# 03_Power.net
KiCad netlist of a schematic drawn in Altium Designer
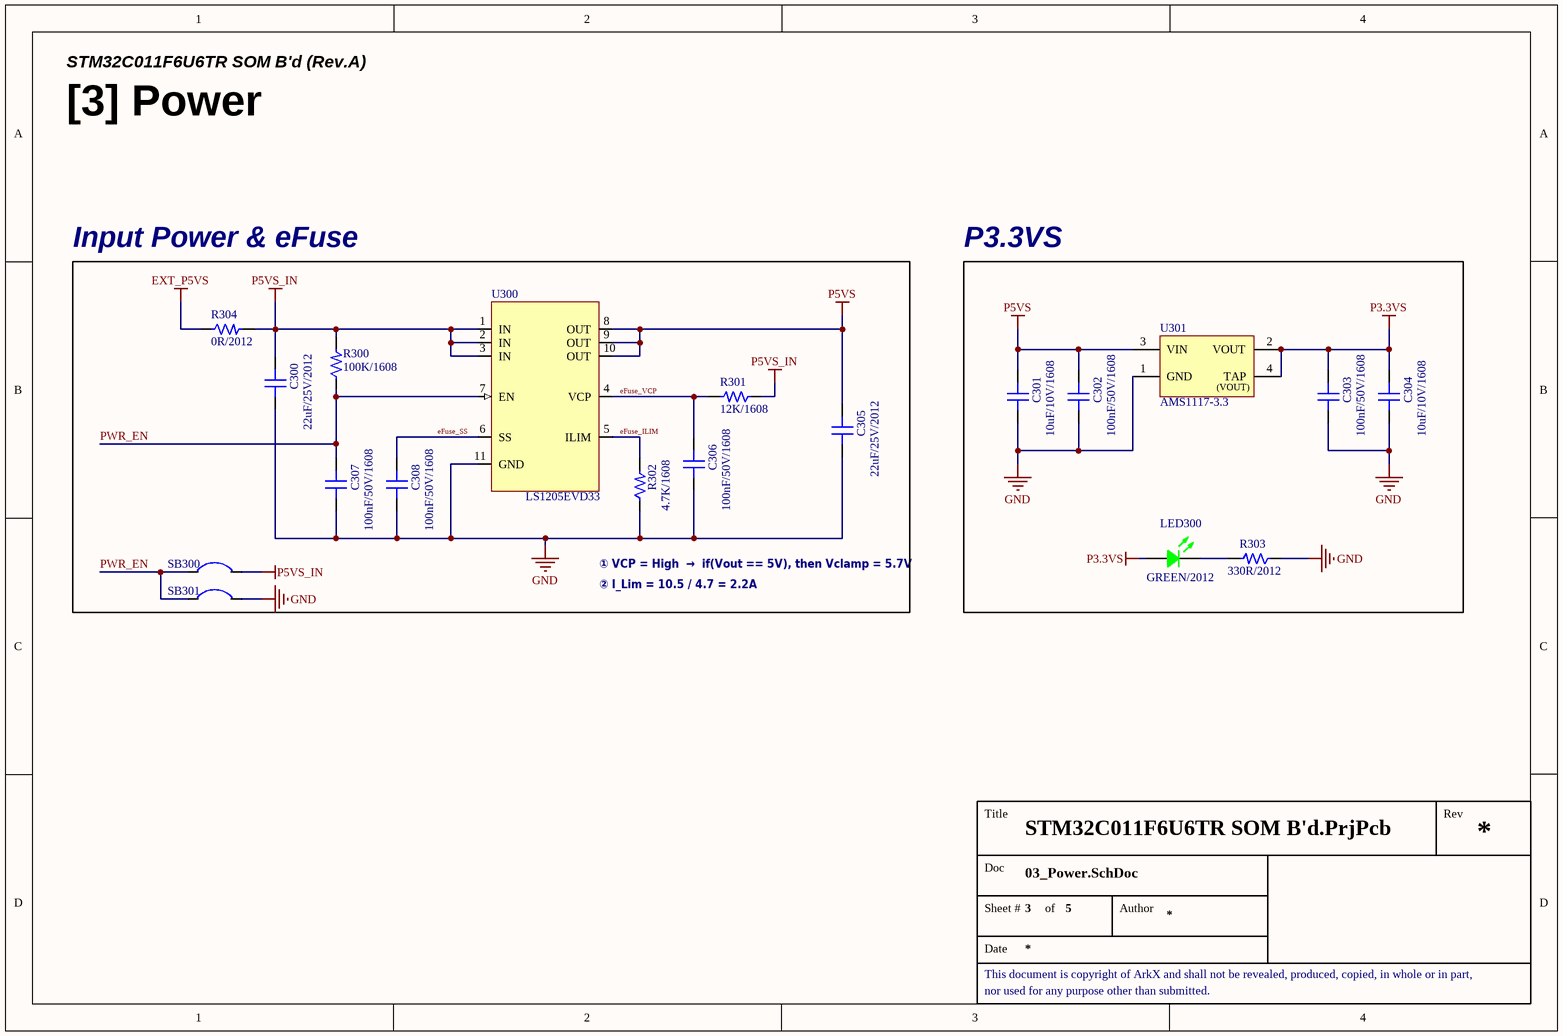
[diagram p0: 03_Power.SchDoc]

(export (version "E")
  (design (tool "Eeschema 10.0.6"))
  (components
    (comp (ref "C300")
      (value "22uF/25V/2012")
      (footprint "CAP 2012 (0805_INCH)")
      (description "Ceramic CAP_22uF/25V/2012")
      (fields (field (name "LCSC PART #") "C45783"))
      (libsource (lib "Arkx") (part "CAP_22uF/25V/2012"))
    )
    (comp (ref "C301")
      (value "10uF/10V/1608")
      (footprint "CAP 1608 (0603_INCH)")
      (description "Ceramic CAP_10uF/10V/1608")
      (fields (field (name "LCSC PART #") "C19702"))
      (libsource (lib "Arkx") (part "CAP_10uF/10V/1608"))
    )
    (comp (ref "C302")
      (value "100nF/50V/1608")
      (footprint "CAP 1608 (0603_INCH)")
      (description "Ceramic CAP_100nF/50V/1608")
      (fields (field (name "LCSC PART #") "C14663"))
      (libsource (lib "Arkx") (part "CAP_100nF/50V/1608"))
    )
    (comp (ref "C303")
      (value "100nF/50V/1608")
      (footprint "CAP 1608 (0603_INCH)")
      (description "Ceramic CAP_100nF/50V/1608")
      (fields (field (name "LCSC PART #") "C14663"))
      (libsource (lib "Arkx") (part "CAP_100nF/50V/1608"))
    )
    (comp (ref "C304")
      (value "10uF/10V/1608")
      (footprint "CAP 1608 (0603_INCH)")
      (description "Ceramic CAP_10uF/10V/1608")
      (fields (field (name "LCSC PART #") "C19702"))
      (libsource (lib "Arkx") (part "CAP_10uF/10V/1608"))
    )
    (comp (ref "C305")
      (value "22uF/25V/2012")
      (footprint "CAP 2012 (0805_INCH)")
      (description "Ceramic CAP_22uF/25V/2012")
      (fields (field (name "LCSC PART #") "C45783"))
      (libsource (lib "Arkx") (part "CAP_22uF/25V/2012"))
    )
    (comp (ref "C306")
      (value "100nF/50V/1608")
      (footprint "CAP 1608 (0603_INCH)")
      (description "Ceramic CAP_100nF/50V/1608")
      (fields (field (name "LCSC PART #") "C14663"))
      (libsource (lib "Arkx") (part "CAP_100nF/50V/1608"))
    )
    (comp (ref "C307")
      (value "100nF/50V/1608")
      (footprint "CAP 1608 (0603_INCH)")
      (description "Ceramic CAP_100nF/50V/1608")
      (fields (field (name "LCSC PART #") "C14663"))
      (libsource (lib "Arkx") (part "CAP_100nF/50V/1608"))
    )
    (comp (ref "C308")
      (value "100nF/50V/1608")
      (footprint "CAP 1608 (0603_INCH)")
      (description "Ceramic CAP_100nF/50V/1608")
      (fields (field (name "LCSC PART #") "C14663"))
      (libsource (lib "Arkx") (part "CAP_100nF/50V/1608"))
    )
    (comp (ref "LED300")
      (value "GREEN/2012")
      (footprint "LED MHT170RGBCT (GREEN)")
      (fields (field (name "LCSC PART #") "C2962094"))
      (libsource (lib "Arkx") (part "LED_MHT170RGBCT(GREEN)"))
    )
    (comp (ref "R300")
      (value "100K/1608")
      (footprint "RES 1608 (0603_inch)")
      (description "RES_100K/1608/0.1W")
      (fields (field (name "LCSC PART #") "C25803"))
      (libsource (lib "Arkx") (part "RES_100K/1608/0.1W"))
    )
    (comp (ref "R301")
      (value "12K/1608")
      (footprint "RES 1608 (0603_inch)")
      (description "RES_12K/1608/0.1W")
      (fields (field (name "LCSC PART #") "C22790"))
      (libsource (lib "Arkx") (part "RES_12K/1608/0.1W"))
    )
    (comp (ref "R302")
      (value "4.7K/1608")
      (footprint "RES 1608 (0603_inch)")
      (description "RES_4.7K/1608/0.1W")
      (fields (field (name "LCSC PART #") "C23162"))
      (libsource (lib "Arkx") (part "RES_4.7K/1608/0.1W"))
    )
    (comp (ref "R303")
      (value "330R/2012")
      (footprint "RES 2012 (0805_inch)")
      (description "RES_330R/2012/0.125W")
      (fields (field (name "LCSC PART #") "C17630"))
      (libsource (lib "Arkx") (part "RES_330R/2012/0.125W"))
    )
    (comp (ref "R304")
      (value "0R/2012")
      (footprint "RES 2012 (0805_inch)")
      (description "RES_0R/2012/0.125W")
      (fields (field (name "LCSC PART #") "C17477"))
      (libsource (lib "Arkx") (part "RES_0R/2012/0.125W"))
    )
    (comp (ref "SB300")
      (value "SB")
      (footprint "SB (Solder-Bridge)")
      (description "SB_Solder-Bridge")
      (libsource (lib "Arkx") (part "SB_Solder-Bridge"))
    )
    (comp (ref "SB301")
      (value "SB")
      (footprint "SB (Solder-Bridge)")
      (description "SB_Solder-Bridge")
      (libsource (lib "Arkx") (part "SB_Solder-Bridge"))
    )
    (comp (ref "U300")
      (value "LS1205EVD33")
      (footprint "IC_DFN_3x3_10L")
      (description "18V, 5A eFuse with Programmable Current Limit and Output Voltage Clamp, 10-DFN (3x3)")
      (libsource (lib "Arkx") (part "IC_eFUSE_LS1205EVD33"))
    )
    (comp (ref "U301")
      (value "AMS1117-3.3")
      (footprint "SOT 223-3 (DIODES INCORPORATED)")
      (fields (field (name "LCSC PART #") "C6186"))
      (libsource (lib "Arkx") (part "IC_REG_AMS1117-3.3"))
    )
  )
  (nets
    (net (code "1") (name "/PWR_EN") (class "Default")
      (node (ref "C307") (pin "2") (pinfunction "2_2") (pintype "passive"))
      (node (ref "R300") (pin "1") (pinfunction "1_1") (pintype "passive"))
      (node (ref "SB300") (pin "1") (pinfunction "1_1") (pintype "passive"))
      (node (ref "SB301") (pin "1") (pinfunction "1_1") (pintype "passive"))
      (node (ref "U300") (pin "7") (pinfunction "EN_7") (pintype "input"))
    )
    (net (code "2") (name "/eFuse_ILIM") (class "Default")
      (node (ref "R302") (pin "2") (pinfunction "2_2") (pintype "passive"))
      (node (ref "U300") (pin "5") (pinfunction "ILIM_5") (pintype "passive"))
    )
    (net (code "3") (name "/eFuse_SS") (class "Default")
      (node (ref "C308") (pin "2") (pinfunction "2_2") (pintype "passive"))
      (node (ref "U300") (pin "6") (pinfunction "SS_6") (pintype "passive"))
    )
    (net (code "4") (name "/eFuse_VCP") (class "Default")
      (node (ref "C306") (pin "2") (pinfunction "2_2") (pintype "passive"))
      (node (ref "R301") (pin "2") (pinfunction "2_2") (pintype "passive"))
      (node (ref "U300") (pin "4") (pinfunction "VCP_4") (pintype "passive"))
    )
    (net (code "5") (name "EXT_P5VS") (class "Default")
      (node (ref "R304") (pin "1") (pinfunction "1_1") (pintype "passive"))
    )
    (net (code "6") (name "GND") (class "Default")
      (node (ref "C300") (pin "1") (pinfunction "1_1") (pintype "passive"))
      (node (ref "C301") (pin "1") (pinfunction "1_1") (pintype "passive"))
      (node (ref "C302") (pin "1") (pinfunction "1_1") (pintype "passive"))
      (node (ref "C303") (pin "1") (pinfunction "1_1") (pintype "passive"))
      (node (ref "C304") (pin "1") (pinfunction "1_1") (pintype "passive"))
      (node (ref "C305") (pin "1") (pinfunction "1_1") (pintype "passive"))
      (node (ref "C306") (pin "1") (pinfunction "1_1") (pintype "passive"))
      (node (ref "C307") (pin "1") (pinfunction "1_1") (pintype "passive"))
      (node (ref "C308") (pin "1") (pinfunction "1_1") (pintype "passive"))
      (node (ref "R302") (pin "1") (pinfunction "1_1") (pintype "passive"))
      (node (ref "R303") (pin "1") (pinfunction "1_1") (pintype "passive"))
      (node (ref "SB301") (pin "2") (pinfunction "2_2") (pintype "passive"))
      (node (ref "U300") (pin "11") (pinfunction "GND_11") (pintype "power_in"))
      (node (ref "U301") (pin "1") (pinfunction "GND_1") (pintype "passive"))
    )
    (net (code "7") (name "Net-(LED300-GREEN)") (class "Default")
      (node (ref "LED300") (pin "2") (pinfunction "GREEN_2") (pintype "passive"))
      (node (ref "R303") (pin "2") (pinfunction "2_2") (pintype "passive"))
    )
    (net (code "8") (name "P3.3VS") (class "Default")
      (node (ref "C303") (pin "2") (pinfunction "2_2") (pintype "passive"))
      (node (ref "C304") (pin "2") (pinfunction "2_2") (pintype "passive"))
      (node (ref "LED300") (pin "4") (pinfunction "Common_Anode_4") (pintype "passive"))
      (node (ref "U301") (pin "2") (pinfunction "VOUT_2") (pintype "passive"))
      (node (ref "U301") (pin "4") (pinfunction "TAP_4") (pintype "passive"))
    )
    (net (code "9") (name "P5VS") (class "Default")
      (node (ref "C301") (pin "2") (pinfunction "2_2") (pintype "passive"))
      (node (ref "C302") (pin "2") (pinfunction "2_2") (pintype "passive"))
      (node (ref "C305") (pin "2") (pinfunction "2_2") (pintype "passive"))
      (node (ref "U300") (pin "10") (pinfunction "OUT_10") (pintype "power_in"))
      (node (ref "U300") (pin "8") (pinfunction "OUT_8") (pintype "power_in"))
      (node (ref "U300") (pin "9") (pinfunction "OUT_9") (pintype "power_in"))
      (node (ref "U301") (pin "3") (pinfunction "VIN_3") (pintype "passive"))
    )
    (net (code "10") (name "P5VS_IN") (class "Default")
      (node (ref "C300") (pin "2") (pinfunction "2_2") (pintype "passive"))
      (node (ref "R300") (pin "2") (pinfunction "2_2") (pintype "passive"))
      (node (ref "R301") (pin "1") (pinfunction "1_1") (pintype "passive"))
      (node (ref "R304") (pin "2") (pinfunction "2_2") (pintype "passive"))
      (node (ref "SB300") (pin "2") (pinfunction "2_2") (pintype "passive"))
      (node (ref "U300") (pin "1") (pinfunction "IN_1") (pintype "power_in"))
      (node (ref "U300") (pin "2") (pinfunction "IN_2") (pintype "power_in"))
      (node (ref "U300") (pin "3") (pinfunction "IN_3") (pintype "power_in"))
    )
  )
)
